# Communication_Module_v2.net
KiCad netlist of a schematic drawn in EAGLE
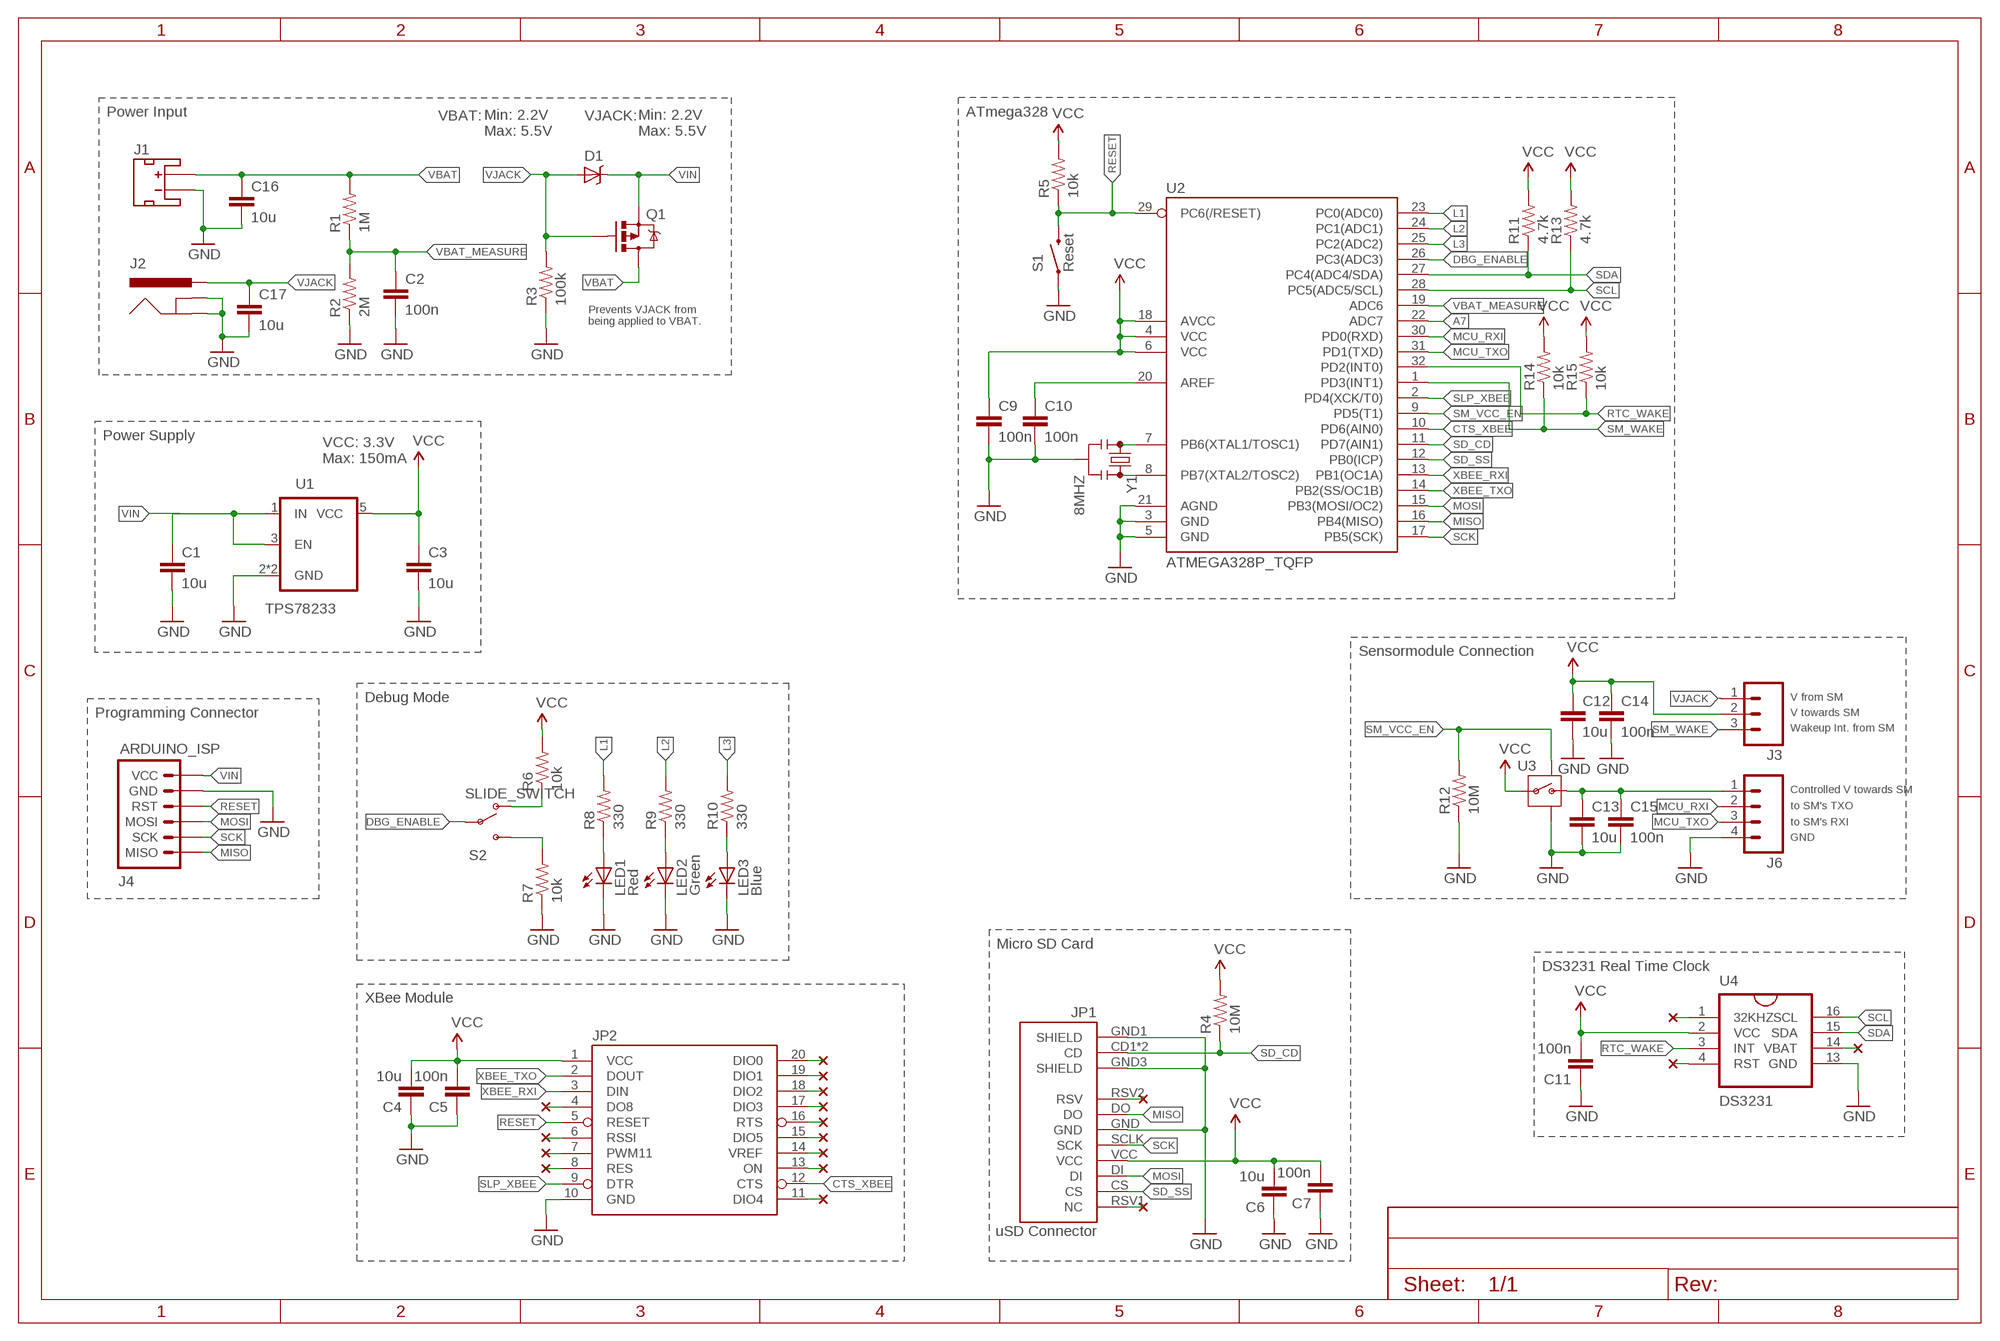
[diagram p0: schematic, sheet 1]

(export (version "E")
  (design (tool "Eeschema 10.0.6"))
  (components
    (comp (ref "C1")
      (value "10u")
      (footprint "eagle-import:C0805")
      (libsource (lib "eagle-import") (part "C"))
    )
    (comp (ref "C2")
      (value "100n")
      (footprint "eagle-import:C0805")
      (libsource (lib "eagle-import") (part "C"))
    )
    (comp (ref "C3")
      (value "10u")
      (footprint "eagle-import:C0805")
      (libsource (lib "eagle-import") (part "C"))
    )
    (comp (ref "C4")
      (value "10u")
      (footprint "eagle-import:C0805")
      (libsource (lib "eagle-import") (part "C"))
    )
    (comp (ref "C5")
      (value "100n")
      (footprint "eagle-import:C0805")
      (libsource (lib "eagle-import") (part "C"))
    )
    (comp (ref "C6")
      (value "10u")
      (footprint "eagle-import:C0805")
      (libsource (lib "eagle-import") (part "C"))
    )
    (comp (ref "C7")
      (value "100n")
      (footprint "eagle-import:C0805")
      (libsource (lib "eagle-import") (part "C"))
    )
    (comp (ref "C9")
      (value "100n")
      (footprint "eagle-import:C0805")
      (libsource (lib "eagle-import") (part "C"))
    )
    (comp (ref "C10")
      (value "100n")
      (footprint "eagle-import:C0805")
      (libsource (lib "eagle-import") (part "C"))
    )
    (comp (ref "C11")
      (value "100n")
      (footprint "eagle-import:C0805")
      (libsource (lib "eagle-import") (part "C"))
    )
    (comp (ref "C12")
      (value "10u")
      (footprint "eagle-import:C0805")
      (libsource (lib "eagle-import") (part "C"))
    )
    (comp (ref "C13")
      (value "10u")
      (footprint "eagle-import:C0805")
      (libsource (lib "eagle-import") (part "C"))
    )
    (comp (ref "C14")
      (value "100n")
      (footprint "eagle-import:C0805")
      (libsource (lib "eagle-import") (part "C"))
    )
    (comp (ref "C15")
      (value "100n")
      (footprint "eagle-import:C0805")
      (libsource (lib "eagle-import") (part "C"))
    )
    (comp (ref "C16")
      (value "10u")
      (footprint "eagle-import:C0805")
      (libsource (lib "eagle-import") (part "C"))
    )
    (comp (ref "C17")
      (value "10u")
      (footprint "eagle-import:C0805")
      (libsource (lib "eagle-import") (part "C"))
    )
    (comp (ref "D1")
      (value "DIODE-SCHOTTKY")
      (footprint "eagle-import:0603-DIODE")
      (libsource (lib "eagle-import") (part "DIODE-SCHOTTKY"))
    )
    (comp (ref "J1")
      (value "JST_2MM_MALE")
      (footprint "eagle-import:JST-2-SMD")
      (libsource (lib "eagle-import") (part "JST_2MM_MALE"))
    )
    (comp (ref "J2")
      (value "5.5x2.1mm Barrel")
      (footprint "eagle-import:POWER_JACK_SMD")
      (libsource (lib "eagle-import") (part "POWER_JACKSMD"))
    )
    (comp (ref "J3")
      (value "M03PTH")
      (footprint "eagle-import:1X03")
      (libsource (lib "eagle-import") (part "M03PTH"))
    )
    (comp (ref "J4")
      (value "ARDUINO_ISP")
      (footprint "eagle-import:M-2X3")
      (libsource (lib "eagle-import") (part "ARDUINO_ISP"))
    )
    (comp (ref "J6")
      (value "M04PTH")
      (footprint "eagle-import:1X04")
      (libsource (lib "eagle-import") (part "M04PTH"))
    )
    (comp (ref "JP1")
      (value "USD-SOCKETNEW")
      (footprint "eagle-import:MICRO-SD-SOCKET-PP")
      (libsource (lib "eagle-import") (part "USD-SOCKETNEW"))
    )
    (comp (ref "JP2")
      (value "XBEEB3")
      (footprint "eagle-import:XBEE-SMD")
      (libsource (lib "eagle-import") (part "XBEEB3"))
    )
    (comp (ref "LED1")
      (value "Red")
      (footprint "eagle-import:SML0805")
      (libsource (lib "eagle-import") (part "LEDSML0805"))
    )
    (comp (ref "LED2")
      (value "Green")
      (footprint "eagle-import:SML0805")
      (libsource (lib "eagle-import") (part "LEDSML0805"))
    )
    (comp (ref "LED3")
      (value "Blue")
      (footprint "eagle-import:SML0805")
      (libsource (lib "eagle-import") (part "LEDSML0805"))
    )
    (comp (ref "Q1")
      (value "PFET")
      (footprint "eagle-import:SOT23-3")
      (libsource (lib "eagle-import") (part "MOSFET-PCHANNELSMD"))
    )
    (comp (ref "R1")
      (value "1M")
      (footprint "eagle-import:0805")
      (libsource (lib "eagle-import") (part "RESISTOR0805-RES"))
    )
    (comp (ref "R2")
      (value "2M")
      (footprint "eagle-import:0805")
      (libsource (lib "eagle-import") (part "RESISTOR0805-RES"))
    )
    (comp (ref "R3")
      (value "100k")
      (footprint "eagle-import:0805")
      (libsource (lib "eagle-import") (part "RESISTOR0805-RES"))
    )
    (comp (ref "R4")
      (value "10M")
      (footprint "eagle-import:0805")
      (libsource (lib "eagle-import") (part "RESISTOR0805-RES"))
    )
    (comp (ref "R5")
      (value "10k")
      (footprint "eagle-import:0805")
      (libsource (lib "eagle-import") (part "RESISTOR0805-RES"))
    )
    (comp (ref "R6")
      (value "10k")
      (footprint "eagle-import:0805")
      (libsource (lib "eagle-import") (part "RESISTOR0805-RES"))
    )
    (comp (ref "R7")
      (value "10k")
      (footprint "eagle-import:0805")
      (libsource (lib "eagle-import") (part "RESISTOR0805-RES"))
    )
    (comp (ref "R8")
      (value "330")
      (footprint "eagle-import:0805")
      (libsource (lib "eagle-import") (part "RESISTOR0805-RES"))
    )
    (comp (ref "R9")
      (value "330")
      (footprint "eagle-import:0805")
      (libsource (lib "eagle-import") (part "RESISTOR0805-RES"))
    )
    (comp (ref "R10")
      (value "330")
      (footprint "eagle-import:0805")
      (libsource (lib "eagle-import") (part "RESISTOR0805-RES"))
    )
    (comp (ref "R11")
      (value "4.7k")
      (footprint "eagle-import:0805")
      (libsource (lib "eagle-import") (part "RESISTOR0805-RES"))
    )
    (comp (ref "R12")
      (value "10M")
      (footprint "eagle-import:0805")
      (libsource (lib "eagle-import") (part "RESISTOR0805-RES"))
    )
    (comp (ref "R13")
      (value "4.7k")
      (footprint "eagle-import:0805")
      (libsource (lib "eagle-import") (part "RESISTOR0805-RES"))
    )
    (comp (ref "R14")
      (value "10k")
      (footprint "eagle-import:0805")
      (libsource (lib "eagle-import") (part "RESISTOR0805-RES"))
    )
    (comp (ref "R15")
      (value "10k")
      (footprint "eagle-import:0805")
      (libsource (lib "eagle-import") (part "RESISTOR0805-RES"))
    )
    (comp (ref "S1")
      (value "Reset")
      (footprint "eagle-import:M-PUSHBUTTON-SMD")
      (libsource (lib "eagle-import") (part "PUSHBUTTON"))
    )
    (comp (ref "S2")
      (value "SLIDE_SWITCH")
      (footprint "eagle-import:P-JS202011SCQN")
      (libsource (lib "eagle-import") (part "SLIDE_SWITCH"))
    )
    (comp (ref "U1")
      (value "TPS78233")
      (footprint "eagle-import:SOT23-5")
      (libsource (lib "eagle-import") (part "TPS78233"))
    )
    (comp (ref "U2")
      (value "ATMEGA328P_TQFP")
      (footprint "eagle-import:TQFP32-08")
      (libsource (lib "eagle-import") (part "ATMEGA328P_TQFP"))
    )
    (comp (ref "U3")
      (value "SIP32431")
      (footprint "eagle-import:SC70")
      (libsource (lib "eagle-import") (part "SIP32431"))
    )
    (comp (ref "U4")
      (value "DS3231SOIC16")
      (footprint "eagle-import:SO016")
      (libsource (lib "eagle-import") (part "DS3231SOIC16"))
    )
    (comp (ref "Y1")
      (value "8MHZ")
      (footprint "eagle-import:RESONATOR-SMD")
      (libsource (lib "eagle-import") (part "RESONATOR8MHZ"))
    )
  )
  (nets
    (net (code "1") (name "A7") (class "Default")
      (node (ref "U2") (pin "22") (pinfunction "ADC7_22") (pintype "bidirectional"))
    )
    (net (code "2") (name "CTS_XBEE") (class "Default")
      (node (ref "JP2") (pin "12") (pinfunction "CTS_12") (pintype "output"))
      (node (ref "U2") (pin "10") (pinfunction "PD6(AIN0)_10") (pintype "bidirectional"))
    )
    (net (code "3") (name "DBG_ENABLE") (class "Default")
      (node (ref "S2") (pin "P$2") (pinfunction "MIDDLE_P$2") (pintype "passive"))
      (node (ref "S2") (pin "P$5") (pinfunction "MIDDLE_P$5") (pintype "passive"))
      (node (ref "U2") (pin "26") (pinfunction "PC3(ADC3)_26") (pintype "bidirectional"))
    )
    (net (code "4") (name "GND") (class "Default")
      (node (ref "C1") (pin "2") (pinfunction "2_2") (pintype "passive"))
      (node (ref "C10") (pin "2") (pinfunction "2_2") (pintype "passive"))
      (node (ref "C11") (pin "1") (pinfunction "1_1") (pintype "passive"))
      (node (ref "C12") (pin "2") (pinfunction "2_2") (pintype "passive"))
      (node (ref "C13") (pin "2") (pinfunction "2_2") (pintype "passive"))
      (node (ref "C14") (pin "2") (pinfunction "2_2") (pintype "passive"))
      (node (ref "C15") (pin "2") (pinfunction "2_2") (pintype "passive"))
      (node (ref "C16") (pin "2") (pinfunction "2_2") (pintype "passive"))
      (node (ref "C17") (pin "2") (pinfunction "2_2") (pintype "passive"))
      (node (ref "C2") (pin "2") (pinfunction "2_2") (pintype "passive"))
      (node (ref "C3") (pin "2") (pinfunction "2_2") (pintype "passive"))
      (node (ref "C4") (pin "1") (pinfunction "1_1") (pintype "passive"))
      (node (ref "C5") (pin "1") (pinfunction "1_1") (pintype "passive"))
      (node (ref "C6") (pin "1") (pinfunction "1_1") (pintype "passive"))
      (node (ref "C7") (pin "1") (pinfunction "1_1") (pintype "passive"))
      (node (ref "C9") (pin "2") (pinfunction "2_2") (pintype "passive"))
      (node (ref "J1") (pin "1") (pinfunction "-_1") (pintype "bidirectional"))
      (node (ref "J2") (pin "GND") (pinfunction "GNDBREAK_GND") (pintype "bidirectional"))
      (node (ref "J2") (pin "P$4") (pinfunction "GND_P$4") (pintype "bidirectional"))
      (node (ref "J4") (pin "P$5") (pinfunction "GND_P$5") (pintype "passive"))
      (node (ref "J6") (pin "4") (pinfunction "4_4") (pintype "passive"))
      (node (ref "JP1") (pin "GND") (pinfunction "GND_GND") (pintype "bidirectional"))
      (node (ref "JP1") (pin "GND1") (pinfunction "SHIELD_GND1") (pintype "bidirectional"))
      (node (ref "JP1") (pin "GND3") (pinfunction "SHIELD_GND3") (pintype "bidirectional"))
      (node (ref "JP2") (pin "10") (pinfunction "GND_10") (pintype "power_in"))
      (node (ref "LED1") (pin "C") (pinfunction "C_C") (pintype "passive"))
      (node (ref "LED2") (pin "C") (pinfunction "C_C") (pintype "passive"))
      (node (ref "LED3") (pin "C") (pinfunction "C_C") (pintype "passive"))
      (node (ref "R12") (pin "1") (pinfunction "1_1") (pintype "passive"))
      (node (ref "R2") (pin "1") (pinfunction "1_1") (pintype "passive"))
      (node (ref "R3") (pin "1") (pinfunction "1_1") (pintype "passive"))
      (node (ref "R7") (pin "1") (pinfunction "1_1") (pintype "passive"))
      (node (ref "S1") (pin "1") (pinfunction "LEFT_1") (pintype "passive"))
      (node (ref "S1") (pin "2") (pinfunction "LEFT_2") (pintype "passive"))
      (node (ref "U1") (pin "2") (pinfunction "GND_2") (pintype "input"))
      (node (ref "U1") (pin "4") (pinfunction "GND_4") (pintype "input"))
      (node (ref "U2") (pin "21") (pinfunction "AGND_21") (pintype "bidirectional"))
      (node (ref "U2") (pin "3") (pinfunction "GND_3") (pintype "bidirectional"))
      (node (ref "U2") (pin "5") (pinfunction "GND_5") (pintype "bidirectional"))
      (node (ref "U3") (pin "2") (pinfunction "GND_2") (pintype "passive"))
      (node (ref "U3") (pin "5") (pinfunction "GND_5") (pintype "passive"))
      (node (ref "U3") (pin "6") (pinfunction "GND_6") (pintype "passive"))
      (node (ref "U4") (pin "13") (pinfunction "GND_13") (pintype "bidirectional"))
      (node (ref "Y1") (pin "2") (pinfunction "2_2") (pintype "passive"))
    )
    (net (code "5") (name "L1") (class "Default")
      (node (ref "R8") (pin "2") (pinfunction "2_2") (pintype "passive"))
      (node (ref "U2") (pin "23") (pinfunction "PC0(ADC0)_23") (pintype "bidirectional"))
    )
    (net (code "6") (name "L2") (class "Default")
      (node (ref "R9") (pin "2") (pinfunction "2_2") (pintype "passive"))
      (node (ref "U2") (pin "24") (pinfunction "PC1(ADC1)_24") (pintype "bidirectional"))
    )
    (net (code "7") (name "L3") (class "Default")
      (node (ref "R10") (pin "2") (pinfunction "2_2") (pintype "passive"))
      (node (ref "U2") (pin "25") (pinfunction "PC2(ADC2)_25") (pintype "bidirectional"))
    )
    (net (code "8") (name "MCU_RXI") (class "Default")
      (node (ref "J6") (pin "2") (pinfunction "2_2") (pintype "passive"))
      (node (ref "U2") (pin "30") (pinfunction "PD0(RXD)_30") (pintype "bidirectional"))
    )
    (net (code "9") (name "MCU_TXO") (class "Default")
      (node (ref "J6") (pin "3") (pinfunction "3_3") (pintype "passive"))
      (node (ref "U2") (pin "31") (pinfunction "PD1(TXD)_31") (pintype "bidirectional"))
    )
    (net (code "10") (name "MISO") (class "Default")
      (node (ref "J4") (pin "P$1") (pinfunction "MISO_P$1") (pintype "passive"))
      (node (ref "JP1") (pin "DO") (pinfunction "DO_DO") (pintype "bidirectional"))
      (node (ref "U2") (pin "16") (pinfunction "PB4(MISO)_16") (pintype "bidirectional"))
    )
    (net (code "11") (name "MOSI") (class "Default")
      (node (ref "J4") (pin "P$3") (pinfunction "MOSI_P$3") (pintype "passive"))
      (node (ref "JP1") (pin "DI") (pinfunction "DI_DI") (pintype "bidirectional"))
      (node (ref "U2") (pin "15") (pinfunction "PB3(MOSI/OC2)_15") (pintype "bidirectional"))
    )
    (net (code "12") (name "Net-(LED1-PadA)") (class "Default")
      (node (ref "LED1") (pin "A") (pinfunction "A_A") (pintype "passive"))
      (node (ref "R8") (pin "1") (pinfunction "1_1") (pintype "passive"))
    )
    (net (code "13") (name "Net-(LED2-PadA)") (class "Default")
      (node (ref "LED2") (pin "A") (pinfunction "A_A") (pintype "passive"))
      (node (ref "R9") (pin "1") (pinfunction "1_1") (pintype "passive"))
    )
    (net (code "14") (name "Net-(LED3-PadA)") (class "Default")
      (node (ref "LED3") (pin "A") (pinfunction "A_A") (pintype "passive"))
      (node (ref "R10") (pin "1") (pinfunction "1_1") (pintype "passive"))
    )
    (net (code "15") (name "Net-(R6-Pad1)") (class "Default")
      (node (ref "R6") (pin "1") (pinfunction "1_1") (pintype "passive"))
      (node (ref "S2") (pin "P$3") (pinfunction "UPPER_P$3") (pintype "passive"))
      (node (ref "S2") (pin "P$6") (pinfunction "UPPER_P$6") (pintype "passive"))
    )
    (net (code "16") (name "Net-(R7-Pad2)") (class "Default")
      (node (ref "R7") (pin "2") (pinfunction "2_2") (pintype "passive"))
      (node (ref "S2") (pin "P$1") (pinfunction "LOWER_P$1") (pintype "passive"))
      (node (ref "S2") (pin "P$4") (pinfunction "LOWER_P$4") (pintype "passive"))
    )
    (net (code "17") (name "Net-(U2-AREF)") (class "Default")
      (node (ref "C10") (pin "1") (pinfunction "1_1") (pintype "passive"))
      (node (ref "U2") (pin "20") (pinfunction "AREF_20") (pintype "bidirectional"))
    )
    (net (code "18") (name "Net-(U2-PB6(XTAL1{slash}TOSC1))") (class "Default")
      (node (ref "U2") (pin "7") (pinfunction "PB6(XTAL1/TOSC1)_7") (pintype "bidirectional"))
      (node (ref "Y1") (pin "1") (pinfunction "1_1") (pintype "passive"))
    )
    (net (code "19") (name "Net-(U2-PB7(XTAL2{slash}TOSC2))") (class "Default")
      (node (ref "U2") (pin "8") (pinfunction "PB7(XTAL2/TOSC2)_8") (pintype "bidirectional"))
      (node (ref "Y1") (pin "3") (pinfunction "3_3") (pintype "passive"))
    )
    (net (code "20") (name "Net-(U3-OUT)") (class "Default")
      (node (ref "C13") (pin "1") (pinfunction "1_1") (pintype "passive"))
      (node (ref "C15") (pin "1") (pinfunction "1_1") (pintype "passive"))
      (node (ref "J6") (pin "1") (pinfunction "1_1") (pintype "passive"))
      (node (ref "U3") (pin "1") (pinfunction "OUT_1") (pintype "passive"))
    )
    (net (code "21") (name "RESET") (class "Default")
      (node (ref "J4") (pin "P$4") (pinfunction "RST_P$4") (pintype "passive"))
      (node (ref "JP2") (pin "5") (pinfunction "RESET_5") (pintype "input"))
      (node (ref "R5") (pin "1") (pinfunction "1_1") (pintype "passive"))
      (node (ref "S1") (pin "3") (pinfunction "RIGHT_3") (pintype "passive"))
      (node (ref "S1") (pin "4") (pinfunction "RIGHT_4") (pintype "passive"))
      (node (ref "U2") (pin "29") (pinfunction "PC6(/RESET)_29") (pintype "bidirectional"))
    )
    (net (code "22") (name "RTC_WAKE") (class "Default")
      (node (ref "R15") (pin "1") (pinfunction "1_1") (pintype "passive"))
      (node (ref "U2") (pin "32") (pinfunction "PD2(INT0)_32") (pintype "bidirectional"))
      (node (ref "U4") (pin "3") (pinfunction "INT_3") (pintype "bidirectional"))
    )
    (net (code "23") (name "SCK") (class "Default")
      (node (ref "J4") (pin "P$2") (pinfunction "SCK_P$2") (pintype "passive"))
      (node (ref "JP1") (pin "SCLK") (pinfunction "SCK_SCLK") (pintype "bidirectional"))
      (node (ref "U2") (pin "17") (pinfunction "PB5(SCK)_17") (pintype "bidirectional"))
    )
    (net (code "24") (name "SCL") (class "Default")
      (node (ref "R13") (pin "1") (pinfunction "1_1") (pintype "passive"))
      (node (ref "U2") (pin "28") (pinfunction "PC5(ADC5/SCL)_28") (pintype "bidirectional"))
      (node (ref "U4") (pin "16") (pinfunction "SCL_16") (pintype "bidirectional"))
    )
    (net (code "25") (name "SDA") (class "Default")
      (node (ref "R11") (pin "1") (pinfunction "1_1") (pintype "passive"))
      (node (ref "U2") (pin "27") (pinfunction "PC4(ADC4/SDA)_27") (pintype "bidirectional"))
      (node (ref "U4") (pin "15") (pinfunction "SDA_15") (pintype "bidirectional"))
    )
    (net (code "26") (name "SD_CD") (class "Default")
      (node (ref "JP1") (pin "CD1") (pinfunction "CD_CD1") (pintype "bidirectional"))
      (node (ref "JP1") (pin "CD2") (pinfunction "CD_CD2") (pintype "bidirectional"))
      (node (ref "R4") (pin "1") (pinfunction "1_1") (pintype "passive"))
      (node (ref "U2") (pin "11") (pinfunction "PD7(AIN1)_11") (pintype "bidirectional"))
    )
    (net (code "27") (name "SD_SS") (class "Default")
      (node (ref "JP1") (pin "CS") (pinfunction "CS_CS") (pintype "bidirectional"))
      (node (ref "U2") (pin "12") (pinfunction "PB0(ICP)_12") (pintype "bidirectional"))
    )
    (net (code "28") (name "SLP_XBEE") (class "Default")
      (node (ref "JP2") (pin "9") (pinfunction "DTR_9") (pintype "bidirectional"))
      (node (ref "U2") (pin "2") (pinfunction "PD4(XCK/T0)_2") (pintype "bidirectional"))
    )
    (net (code "29") (name "SM_VCC_EN") (class "Default")
      (node (ref "R12") (pin "2") (pinfunction "2_2") (pintype "passive"))
      (node (ref "U2") (pin "9") (pinfunction "PD5(T1)_9") (pintype "bidirectional"))
      (node (ref "U3") (pin "3") (pinfunction "ON_3") (pintype "passive"))
    )
    (net (code "30") (name "SM_WAKE") (class "Default")
      (node (ref "J3") (pin "3") (pinfunction "3_3") (pintype "passive"))
      (node (ref "R14") (pin "1") (pinfunction "1_1") (pintype "passive"))
      (node (ref "U2") (pin "1") (pinfunction "PD3(INT1)_1") (pintype "bidirectional"))
    )
    (net (code "31") (name "VBAT") (class "Default")
      (node (ref "C16") (pin "1") (pinfunction "1_1") (pintype "passive"))
      (node (ref "J1") (pin "2") (pinfunction "+_2") (pintype "bidirectional"))
      (node (ref "Q1") (pin "3") (pinfunction "D_3") (pintype "passive"))
      (node (ref "R1") (pin "2") (pinfunction "2_2") (pintype "passive"))
    )
    (net (code "32") (name "VBAT_MEASURE") (class "Default")
      (node (ref "C2") (pin "1") (pinfunction "1_1") (pintype "passive"))
      (node (ref "R1") (pin "1") (pinfunction "1_1") (pintype "passive"))
      (node (ref "R2") (pin "2") (pinfunction "2_2") (pintype "passive"))
      (node (ref "U2") (pin "19") (pinfunction "ADC6_19") (pintype "bidirectional"))
    )
    (net (code "33") (name "VCC") (class "Default")
      (node (ref "C11") (pin "2") (pinfunction "2_2") (pintype "passive"))
      (node (ref "C12") (pin "1") (pinfunction "1_1") (pintype "passive"))
      (node (ref "C14") (pin "1") (pinfunction "1_1") (pintype "passive"))
      (node (ref "C3") (pin "1") (pinfunction "1_1") (pintype "passive"))
      (node (ref "C4") (pin "2") (pinfunction "2_2") (pintype "passive"))
      (node (ref "C5") (pin "2") (pinfunction "2_2") (pintype "passive"))
      (node (ref "C6") (pin "2") (pinfunction "2_2") (pintype "passive"))
      (node (ref "C7") (pin "2") (pinfunction "2_2") (pintype "passive"))
      (node (ref "C9") (pin "1") (pinfunction "1_1") (pintype "passive"))
      (node (ref "J3") (pin "2") (pinfunction "2_2") (pintype "passive"))
      (node (ref "JP1") (pin "VCC") (pinfunction "VCC_VCC") (pintype "bidirectional"))
      (node (ref "JP2") (pin "1") (pinfunction "VCC_1") (pintype "power_in"))
      (node (ref "R11") (pin "2") (pinfunction "2_2") (pintype "passive"))
      (node (ref "R13") (pin "2") (pinfunction "2_2") (pintype "passive"))
      (node (ref "R14") (pin "2") (pinfunction "2_2") (pintype "passive"))
      (node (ref "R15") (pin "2") (pinfunction "2_2") (pintype "passive"))
      (node (ref "R4") (pin "2") (pinfunction "2_2") (pintype "passive"))
      (node (ref "R5") (pin "2") (pinfunction "2_2") (pintype "passive"))
      (node (ref "R6") (pin "2") (pinfunction "2_2") (pintype "passive"))
      (node (ref "U1") (pin "5") (pinfunction "VCC_5") (pintype "power_in"))
      (node (ref "U2") (pin "18") (pinfunction "AVCC_18") (pintype "bidirectional"))
      (node (ref "U2") (pin "4") (pinfunction "VCC_4") (pintype "bidirectional"))
      (node (ref "U2") (pin "6") (pinfunction "VCC_6") (pintype "bidirectional"))
      (node (ref "U3") (pin "4") (pinfunction "IN_4") (pintype "passive"))
      (node (ref "U4") (pin "2") (pinfunction "VCC_2") (pintype "bidirectional"))
    )
    (net (code "34") (name "VIN") (class "Default")
      (node (ref "C1") (pin "1") (pinfunction "1_1") (pintype "passive"))
      (node (ref "D1") (pin "C") (pinfunction "C_C") (pintype "passive"))
      (node (ref "J4") (pin "P$6") (pinfunction "VCC_P$6") (pintype "passive"))
      (node (ref "Q1") (pin "2") (pinfunction "S_2") (pintype "passive"))
      (node (ref "U1") (pin "1") (pinfunction "IN_1") (pintype "input"))
      (node (ref "U1") (pin "3") (pinfunction "EN_3") (pintype "input"))
    )
    (net (code "35") (name "VJACK") (class "Default")
      (node (ref "C17") (pin "1") (pinfunction "1_1") (pintype "passive"))
      (node (ref "D1") (pin "A") (pinfunction "A_A") (pintype "passive"))
      (node (ref "J2") (pin "VIN0") (pinfunction "PWR_VIN0") (pintype "bidirectional"))
      (node (ref "J2") (pin "VIN1") (pinfunction "PWR_VIN1") (pintype "bidirectional"))
      (node (ref "J3") (pin "1") (pinfunction "1_1") (pintype "passive"))
      (node (ref "Q1") (pin "1") (pinfunction "G_1") (pintype "passive"))
      (node (ref "R3") (pin "2") (pinfunction "2_2") (pintype "passive"))
    )
    (net (code "36") (name "XBEE_RXI") (class "Default")
      (node (ref "JP2") (pin "3") (pinfunction "DIN_3") (pintype "input"))
      (node (ref "U2") (pin "13") (pinfunction "PB1(OC1A)_13") (pintype "bidirectional"))
    )
    (net (code "37") (name "XBEE_TXO") (class "Default")
      (node (ref "JP2") (pin "2") (pinfunction "DOUT_2") (pintype "output"))
      (node (ref "U2") (pin "14") (pinfunction "PB2(SS/OC1B)_14") (pintype "bidirectional"))
    )
    (net (code "38") (name "unconnected-(J1-PAD1-PadNC1)") (class "Default")
      (node (ref "J1") (pin "NC1") (pinfunction "PAD1_NC1") (pintype "bidirectional"))
    )
    (net (code "39") (name "unconnected-(J1-PAD2-PadNC2)") (class "Default")
      (node (ref "J1") (pin "NC2") (pinfunction "PAD2_NC2") (pintype "bidirectional"))
    )
    (net (code "40") (name "unconnected-(JP1-NC-PadRSV1)") (class "Default")
      (node (ref "JP1") (pin "RSV1") (pinfunction "NC_RSV1") (pintype "bidirectional"))
    )
    (net (code "41") (name "unconnected-(JP1-RSV-PadRSV2)") (class "Default")
      (node (ref "JP1") (pin "RSV2") (pinfunction "RSV_RSV2") (pintype "bidirectional"))
    )
    (net (code "42") (name "unconnected-(JP2-DIO0-Pad20)") (class "Default")
      (node (ref "JP2") (pin "20") (pinfunction "DIO0_20") (pintype "bidirectional"))
    )
    (net (code "43") (name "unconnected-(JP2-DIO1-Pad19)") (class "Default")
      (node (ref "JP2") (pin "19") (pinfunction "DIO1_19") (pintype "bidirectional"))
    )
    (net (code "44") (name "unconnected-(JP2-DIO2-Pad18)") (class "Default")
      (node (ref "JP2") (pin "18") (pinfunction "DIO2_18") (pintype "bidirectional"))
    )
    (net (code "45") (name "unconnected-(JP2-DIO3-Pad17)") (class "Default")
      (node (ref "JP2") (pin "17") (pinfunction "DIO3_17") (pintype "bidirectional"))
    )
    (net (code "46") (name "unconnected-(JP2-DIO4-Pad11)") (class "Default")
      (node (ref "JP2") (pin "11") (pinfunction "DIO4_11") (pintype "bidirectional"))
    )
    (net (code "47") (name "unconnected-(JP2-DIO5-Pad15)") (class "Default")
      (node (ref "JP2") (pin "15") (pinfunction "DIO5_15") (pintype "bidirectional"))
    )
    (net (code "48") (name "unconnected-(JP2-DO8-Pad4)") (class "Default")
      (node (ref "JP2") (pin "4") (pinfunction "DO8_4") (pintype "bidirectional"))
    )
    (net (code "49") (name "unconnected-(JP2-ON-Pad13)") (class "Default")
      (node (ref "JP2") (pin "13") (pinfunction "ON_13") (pintype "bidirectional"))
    )
    (net (code "50") (name "unconnected-(JP2-PWM11-Pad7)") (class "Default")
      (node (ref "JP2") (pin "7") (pinfunction "PWM11_7") (pintype "bidirectional"))
    )
    (net (code "51") (name "unconnected-(JP2-RES-Pad8)") (class "Default")
      (node (ref "JP2") (pin "8") (pinfunction "RES_8") (pintype "bidirectional"))
    )
    (net (code "52") (name "unconnected-(JP2-RSSI-Pad6)") (class "Default")
      (node (ref "JP2") (pin "6") (pinfunction "RSSI_6") (pintype "bidirectional"))
    )
    (net (code "53") (name "unconnected-(JP2-RTS-Pad16)") (class "Default")
      (node (ref "JP2") (pin "16") (pinfunction "RTS_16") (pintype "input"))
    )
    (net (code "54") (name "unconnected-(JP2-VREF-Pad14)") (class "Default")
      (node (ref "JP2") (pin "14") (pinfunction "VREF_14") (pintype "bidirectional"))
    )
    (net (code "55") (name "unconnected-(U4-32KHZ-Pad1)") (class "Default")
      (node (ref "U4") (pin "1") (pinfunction "32KHZ_1") (pintype "bidirectional"))
    )
    (net (code "56") (name "unconnected-(U4-RST-Pad4)") (class "Default")
      (node (ref "U4") (pin "4") (pinfunction "RST_4") (pintype "bidirectional"))
    )
    (net (code "57") (name "unconnected-(U4-VBAT-Pad14)") (class "Default")
      (node (ref "U4") (pin "14") (pinfunction "VBAT_14") (pintype "bidirectional"))
    )
  )
)
